# PCB_JTAG1D.net
KiCad netlist of a schematic drawn in Altium Designer
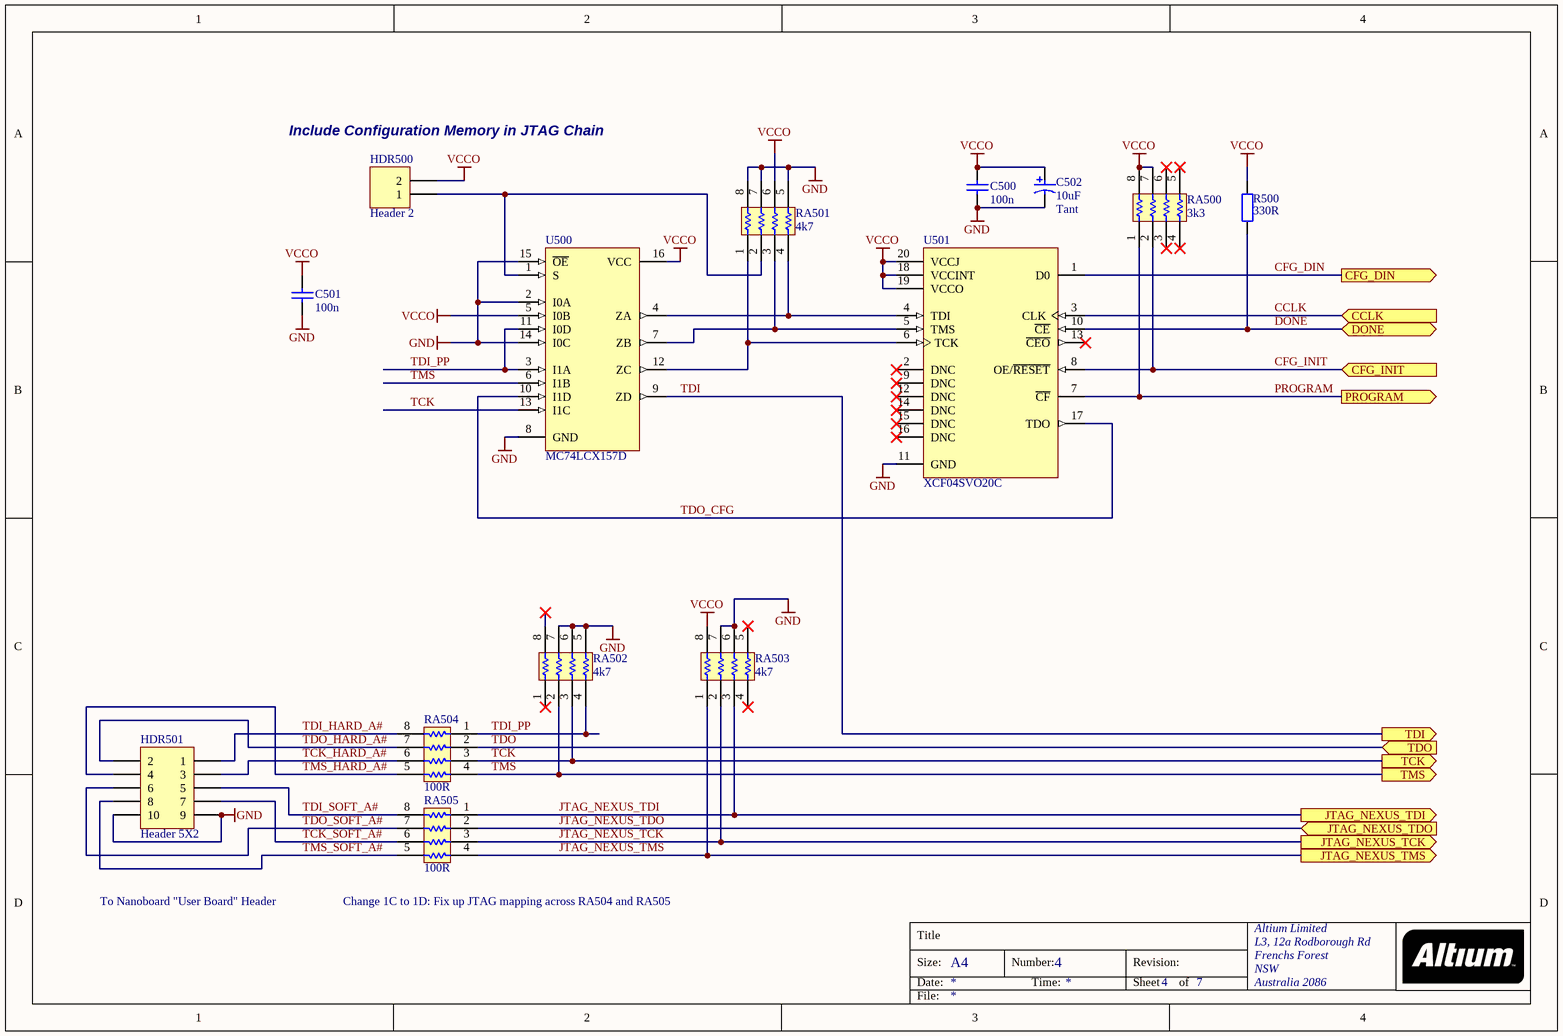
[diagram p0: PCB_JTAG1D.SchDoc]

(export (version "E")
  (design (tool "Eeschema 10.0.6"))
  (components
    (comp (ref "C500")
      (value "100n")
      (footprint "BOC1_3:CC2012-0805")
      (description "Capacitor")
      (libsource (lib "Miscellaneous Devices") (part "CAP"))
    )
    (comp (ref "C501")
      (value "100n")
      (footprint "BOC1_3:CC2012-0805")
      (description "Capacitor")
      (libsource (lib "Miscellaneous Devices") (part "CAP"))
    )
    (comp (ref "C502")
      (value "10uF")
      (footprint "BOC1_3:MCCT-B")
      (description "Polar Capacitor")
      (fields (field (name "CAPACITOR TYPE") "Tant"))
      (libsource (lib "BOC1_3") (part "CAP_POLAR"))
    )
    (comp (ref "HDR500")
      (value "Header 2")
      (footprint "BOC1_3:HDR1X2")
      (description "Header, 2-Pin")
      (fields
        (field (name "MANUFACTURER") "Generic Components")
        (field (name "USAGE") "Include Configuration Memory in JTAG Chain")
        (field (name "PUBLISHER") "Altium Limited")
      )
      (libsource (lib "Miscellaneous Connectors") (part "Header 2"))
    )
    (comp (ref "HDR501")
      (value "Header 5X2")
      (footprint "BOC1_3:HDR2X5")
      (description "Header, 5-Pin, Dual row")
      (fields
        (field (name "MANUFACTURER") "Generic Components")
        (field (name "USAGE") "To Nanoboard \"User Board\" Header")
        (field (name "PUBLISHER") "Altium Limited")
      )
      (libsource (lib "Miscellaneous Connectors") (part "Header 5X2"))
    )
    (comp (ref "R500")
      (value "330R")
      (footprint "BOC1_3:CC2012-0805")
      (description "Resistor")
      (fields (field (name "MANUFACTURER") "Generic Components") (field (name "PUBLISHER") "Altium Limited"))
      (libsource (lib "Miscellaneous Devices") (part "Res2"))
    )
    (comp (ref "RA500")
      (value "3k3")
      (footprint "BOC1_3:MNR34")
      (description "3216x4 Resistor Array")
      (libsource (lib "") (part "MNR34_1"))
    )
    (comp (ref "RA501")
      (value "4k7")
      (footprint "BOC1_3:MNR34")
      (description "3216x4 Resistor Array")
      (libsource (lib "") (part "MNR34_1"))
    )
    (comp (ref "RA502")
      (value "4k7")
      (footprint "BOC1_3:MNR34")
      (description "3216x4 Resistor Array")
      (libsource (lib "") (part "MNR34_1"))
    )
    (comp (ref "RA503")
      (value "4k7")
      (footprint "BOC1_3:MNR34")
      (description "3216x4 Resistor Array")
      (libsource (lib "") (part "MNR34_1"))
    )
    (comp (ref "RA504")
      (value "100R")
      (footprint "BOC1_3:MNR34")
      (description "3216x4 Resistor Array")
      (libsource (lib "BOC1_3") (part "MNR34"))
    )
    (comp (ref "RA505")
      (value "100R")
      (footprint "BOC1_3:MNR34")
      (description "3216x4 Resistor Array")
      (libsource (lib "BOC1_3") (part "MNR34"))
    )
    (comp (ref "U500")
      (value "MC74LCX157D")
      (footprint "751B-05")
      (description "Low-Voltage Quad 2-Input Multiplexer with 5V-Tolerant Inputs (Non-Inverting)")
      (fields (field (name "MANUFACTURER") "ON Semiconductor") (field (name "PUBLISHER") "Altium Limited"))
      (libsource (lib "ON Semi Logic Multiplexer") (part "MC74LCX157D"))
    )
    (comp (ref "U501")
      (value "XCF04SVO20C")
      (footprint "BOC1_3:VO20")
      (fields (field (name "MANUFACTURER") "Xilinx") (field (name "PUBLISHER") "Altium Limited"))
      (libsource (lib "Xilinx XCF00S") (part "XCF04SVO20C"))
    )
  )
  (nets
    (net (code "1") (name "/CCLK") (class "Default")
      (node (ref "U501") (pin "3") (pinfunction "CLK_3") (pintype "input"))
    )
    (net (code "2") (name "/CFG_DIN") (class "Default")
      (node (ref "U501") (pin "1") (pinfunction "D0_1") (pintype "tri_state"))
    )
    (net (code "3") (name "/CFG_INIT") (class "Default")
      (node (ref "RA500") (pin "2") (pintype "passive"))
      (node (ref "U501") (pin "8") (pinfunction "OE/~{RESET}_8") (pintype "input"))
    )
    (net (code "4") (name "/DONE") (class "Default")
      (node (ref "R500") (pin "2") (pinfunction "2_2") (pintype "passive"))
      (node (ref "U501") (pin "10") (pinfunction "~{CE}_10") (pintype "input"))
    )
    (net (code "5") (name "/JTAG_NEXUS_TCK") (class "Default")
      (node (ref "RA503") (pin "2") (pintype "passive"))
      (node (ref "RA505") (pin "3") (pintype "passive"))
    )
    (net (code "6") (name "/JTAG_NEXUS_TDI") (class "Default")
      (node (ref "RA503") (pin "3") (pintype "passive"))
      (node (ref "RA505") (pin "1") (pintype "passive"))
    )
    (net (code "7") (name "/JTAG_NEXUS_TDO") (class "Default")
      (node (ref "RA505") (pin "2") (pintype "passive"))
    )
    (net (code "8") (name "/JTAG_NEXUS_TMS") (class "Default")
      (node (ref "RA503") (pin "1") (pintype "passive"))
      (node (ref "RA505") (pin "4") (pintype "passive"))
    )
    (net (code "9") (name "/PROGRAM") (class "Default")
      (node (ref "RA500") (pin "1") (pintype "passive"))
      (node (ref "U501") (pin "7") (pinfunction "~{CF}_7") (pintype "open_collector"))
    )
    (net (code "10") (name "/TCK") (class "Default")
      (node (ref "RA502") (pin "3") (pintype "passive"))
      (node (ref "RA504") (pin "3") (pintype "passive"))
      (node (ref "U500") (pin "13") (pinfunction "I1C_13") (pintype "input"))
    )
    (net (code "11") (name "/TCK_HARD_A#") (class "Default")
      (node (ref "HDR501") (pin "3") (pinfunction "3_3") (pintype "passive"))
      (node (ref "RA504") (pin "6") (pintype "passive"))
    )
    (net (code "12") (name "/TCK_SOFT_A#") (class "Default")
      (node (ref "HDR501") (pin "7") (pinfunction "7_7") (pintype "passive"))
      (node (ref "RA505") (pin "6") (pintype "passive"))
    )
    (net (code "13") (name "/TDI") (class "Default")
      (node (ref "U500") (pin "9") (pinfunction "ZD_9") (pintype "output"))
    )
    (net (code "14") (name "/TDI_HARD_A#") (class "Default")
      (node (ref "HDR501") (pin "1") (pinfunction "1_1") (pintype "passive"))
      (node (ref "RA504") (pin "8") (pintype "passive"))
    )
    (net (code "15") (name "/TDI_PP") (class "Default")
      (node (ref "RA502") (pin "4") (pintype "passive"))
      (node (ref "RA504") (pin "1") (pintype "passive"))
      (node (ref "U500") (pin "11") (pinfunction "I0D_11") (pintype "input"))
      (node (ref "U500") (pin "3") (pinfunction "I1A_3") (pintype "input"))
    )
    (net (code "16") (name "/TDI_SOFT_A#") (class "Default")
      (node (ref "HDR501") (pin "5") (pinfunction "5_5") (pintype "passive"))
      (node (ref "RA505") (pin "8") (pintype "passive"))
    )
    (net (code "17") (name "/TDO") (class "Default") (node (ref "RA504") (pin "2") (pintype "passive")))
    (net (code "18") (name "/TDO_CFG") (class "Default")
      (node (ref "U500") (pin "10") (pinfunction "I1D_10") (pintype "input"))
      (node (ref "U501") (pin "17") (pinfunction "TDO_17") (pintype "output"))
    )
    (net (code "19") (name "/TDO_HARD_A#") (class "Default")
      (node (ref "HDR501") (pin "2") (pinfunction "2_2") (pintype "passive"))
      (node (ref "RA504") (pin "7") (pintype "passive"))
    )
    (net (code "20") (name "/TDO_SOFT_A#") (class "Default")
      (node (ref "HDR501") (pin "6") (pinfunction "6_6") (pintype "passive"))
      (node (ref "RA505") (pin "7") (pintype "passive"))
    )
    (net (code "21") (name "/TMS") (class "Default")
      (node (ref "RA502") (pin "2") (pintype "passive"))
      (node (ref "RA504") (pin "4") (pintype "passive"))
      (node (ref "U500") (pin "6") (pinfunction "I1B_6") (pintype "input"))
    )
    (net (code "22") (name "/TMS_HARD_A#") (class "Default")
      (node (ref "HDR501") (pin "4") (pinfunction "4_4") (pintype "passive"))
      (node (ref "RA504") (pin "5") (pintype "passive"))
    )
    (net (code "23") (name "/TMS_SOFT_A#") (class "Default")
      (node (ref "HDR501") (pin "8") (pinfunction "8_8") (pintype "passive"))
      (node (ref "RA505") (pin "5") (pintype "passive"))
    )
    (net (code "24") (name "GND") (class "Default")
      (node (ref "C500") (pin "2") (pinfunction "2_2") (pintype "passive"))
      (node (ref "C501") (pin "2") (pinfunction "2_2") (pintype "passive"))
      (node (ref "C502") (pin "2") (pinfunction "2_2") (pintype "passive"))
      (node (ref "HDR501") (pin "10") (pinfunction "10_10") (pintype "passive"))
      (node (ref "HDR501") (pin "9") (pinfunction "9_9") (pintype "passive"))
      (node (ref "RA501") (pin "5") (pintype "passive"))
      (node (ref "RA501") (pin "7") (pintype "passive"))
      (node (ref "RA501") (pin "8") (pintype "passive"))
      (node (ref "RA502") (pin "5") (pintype "passive"))
      (node (ref "RA502") (pin "6") (pintype "passive"))
      (node (ref "RA502") (pin "7") (pintype "passive"))
      (node (ref "RA503") (pin "6") (pintype "passive"))
      (node (ref "RA503") (pin "7") (pintype "passive"))
      (node (ref "U500") (pin "14") (pinfunction "I0C_14") (pintype "input"))
      (node (ref "U500") (pin "15") (pinfunction "~{OE}_15") (pintype "input"))
      (node (ref "U500") (pin "2") (pinfunction "I0A_2") (pintype "input"))
      (node (ref "U500") (pin "8") (pinfunction "GND_8") (pintype "power_in"))
      (node (ref "U501") (pin "11") (pinfunction "GND_11") (pintype "power_in"))
    )
    (net (code "25") (name "Net-(U500-S)") (class "Default")
      (node (ref "HDR500") (pin "1") (pinfunction "1_1") (pintype "passive"))
      (node (ref "RA501") (pin "2") (pintype "passive"))
      (node (ref "U500") (pin "1") (pinfunction "S_1") (pintype "input"))
    )
    (net (code "26") (name "Net-(U500-ZA)") (class "Default")
      (node (ref "RA501") (pin "4") (pintype "passive"))
      (node (ref "U500") (pin "4") (pinfunction "ZA_4") (pintype "output"))
      (node (ref "U501") (pin "4") (pinfunction "TDI_4") (pintype "input"))
    )
    (net (code "27") (name "Net-(U500-ZB)") (class "Default")
      (node (ref "RA501") (pin "3") (pintype "passive"))
      (node (ref "U500") (pin "7") (pinfunction "ZB_7") (pintype "output"))
      (node (ref "U501") (pin "5") (pinfunction "TMS_5") (pintype "input"))
    )
    (net (code "28") (name "Net-(U500-ZC)") (class "Default")
      (node (ref "RA501") (pin "1") (pintype "passive"))
      (node (ref "U500") (pin "12") (pinfunction "ZC_12") (pintype "output"))
      (node (ref "U501") (pin "6") (pinfunction "TCK_6") (pintype "input"))
    )
    (net (code "29") (name "VCCO") (class "Default")
      (node (ref "C500") (pin "1") (pinfunction "1_1") (pintype "passive"))
      (node (ref "C501") (pin "1") (pinfunction "1_1") (pintype "passive"))
      (node (ref "C502") (pin "1") (pinfunction "1_1") (pintype "passive"))
      (node (ref "HDR500") (pin "2") (pinfunction "2_2") (pintype "passive"))
      (node (ref "R500") (pin "1") (pinfunction "1_1") (pintype "passive"))
      (node (ref "RA500") (pin "7") (pintype "passive"))
      (node (ref "RA500") (pin "8") (pintype "passive"))
      (node (ref "RA501") (pin "6") (pintype "passive"))
      (node (ref "RA503") (pin "8") (pintype "passive"))
      (node (ref "U500") (pin "16") (pinfunction "VCC_16") (pintype "power_in"))
      (node (ref "U500") (pin "5") (pinfunction "I0B_5") (pintype "input"))
      (node (ref "U501") (pin "18") (pinfunction "VCCINT_18") (pintype "power_in"))
      (node (ref "U501") (pin "19") (pinfunction "VCCO_19") (pintype "power_in"))
      (node (ref "U501") (pin "20") (pinfunction "VCCJ_20") (pintype "power_in"))
    )
    (net (code "30") (name "unconnected-(RA500-Pad3)") (class "Default")
      (node (ref "RA500") (pin "3") (pintype "passive+no_connect"))
    )
    (net (code "31") (name "unconnected-(RA500-Pad4)") (class "Default")
      (node (ref "RA500") (pin "4") (pintype "passive+no_connect"))
    )
    (net (code "32") (name "unconnected-(RA500-Pad5)") (class "Default")
      (node (ref "RA500") (pin "5") (pintype "passive+no_connect"))
    )
    (net (code "33") (name "unconnected-(RA500-Pad6)") (class "Default")
      (node (ref "RA500") (pin "6") (pintype "passive+no_connect"))
    )
    (net (code "34") (name "unconnected-(RA502-Pad1)") (class "Default")
      (node (ref "RA502") (pin "1") (pintype "passive+no_connect"))
    )
    (net (code "35") (name "unconnected-(RA502-Pad8)") (class "Default")
      (node (ref "RA502") (pin "8") (pintype "passive+no_connect"))
    )
    (net (code "36") (name "unconnected-(RA503-Pad4)") (class "Default")
      (node (ref "RA503") (pin "4") (pintype "passive+no_connect"))
    )
    (net (code "37") (name "unconnected-(RA503-Pad5)") (class "Default")
      (node (ref "RA503") (pin "5") (pintype "passive+no_connect"))
    )
    (net (code "38") (name "unconnected-(U501-DNC-Pad2)") (class "Default")
      (node (ref "U501") (pin "2") (pinfunction "DNC_2") (pintype "passive+no_connect"))
    )
    (net (code "39") (name "unconnected-(U501-DNC-Pad9)") (class "Default")
      (node (ref "U501") (pin "9") (pinfunction "DNC_9") (pintype "passive+no_connect"))
    )
    (net (code "40") (name "unconnected-(U501-DNC-Pad12)") (class "Default")
      (node (ref "U501") (pin "12") (pinfunction "DNC_12") (pintype "passive+no_connect"))
    )
    (net (code "41") (name "unconnected-(U501-DNC-Pad14)") (class "Default")
      (node (ref "U501") (pin "14") (pinfunction "DNC_14") (pintype "passive+no_connect"))
    )
    (net (code "42") (name "unconnected-(U501-DNC-Pad15)") (class "Default")
      (node (ref "U501") (pin "15") (pinfunction "DNC_15") (pintype "passive+no_connect"))
    )
    (net (code "43") (name "unconnected-(U501-DNC-Pad16)") (class "Default")
      (node (ref "U501") (pin "16") (pinfunction "DNC_16") (pintype "passive+no_connect"))
    )
    (net (code "44") (name "unconnected-(U501-~{CEO}-Pad13)") (class "Default")
      (node (ref "U501") (pin "13") (pinfunction "~{CEO}_13") (pintype "output+no_connect"))
    )
  )
)
